# mLRS-dualE28-board02-v011.net
KiCad netlist of a schematic drawn in EAGLE
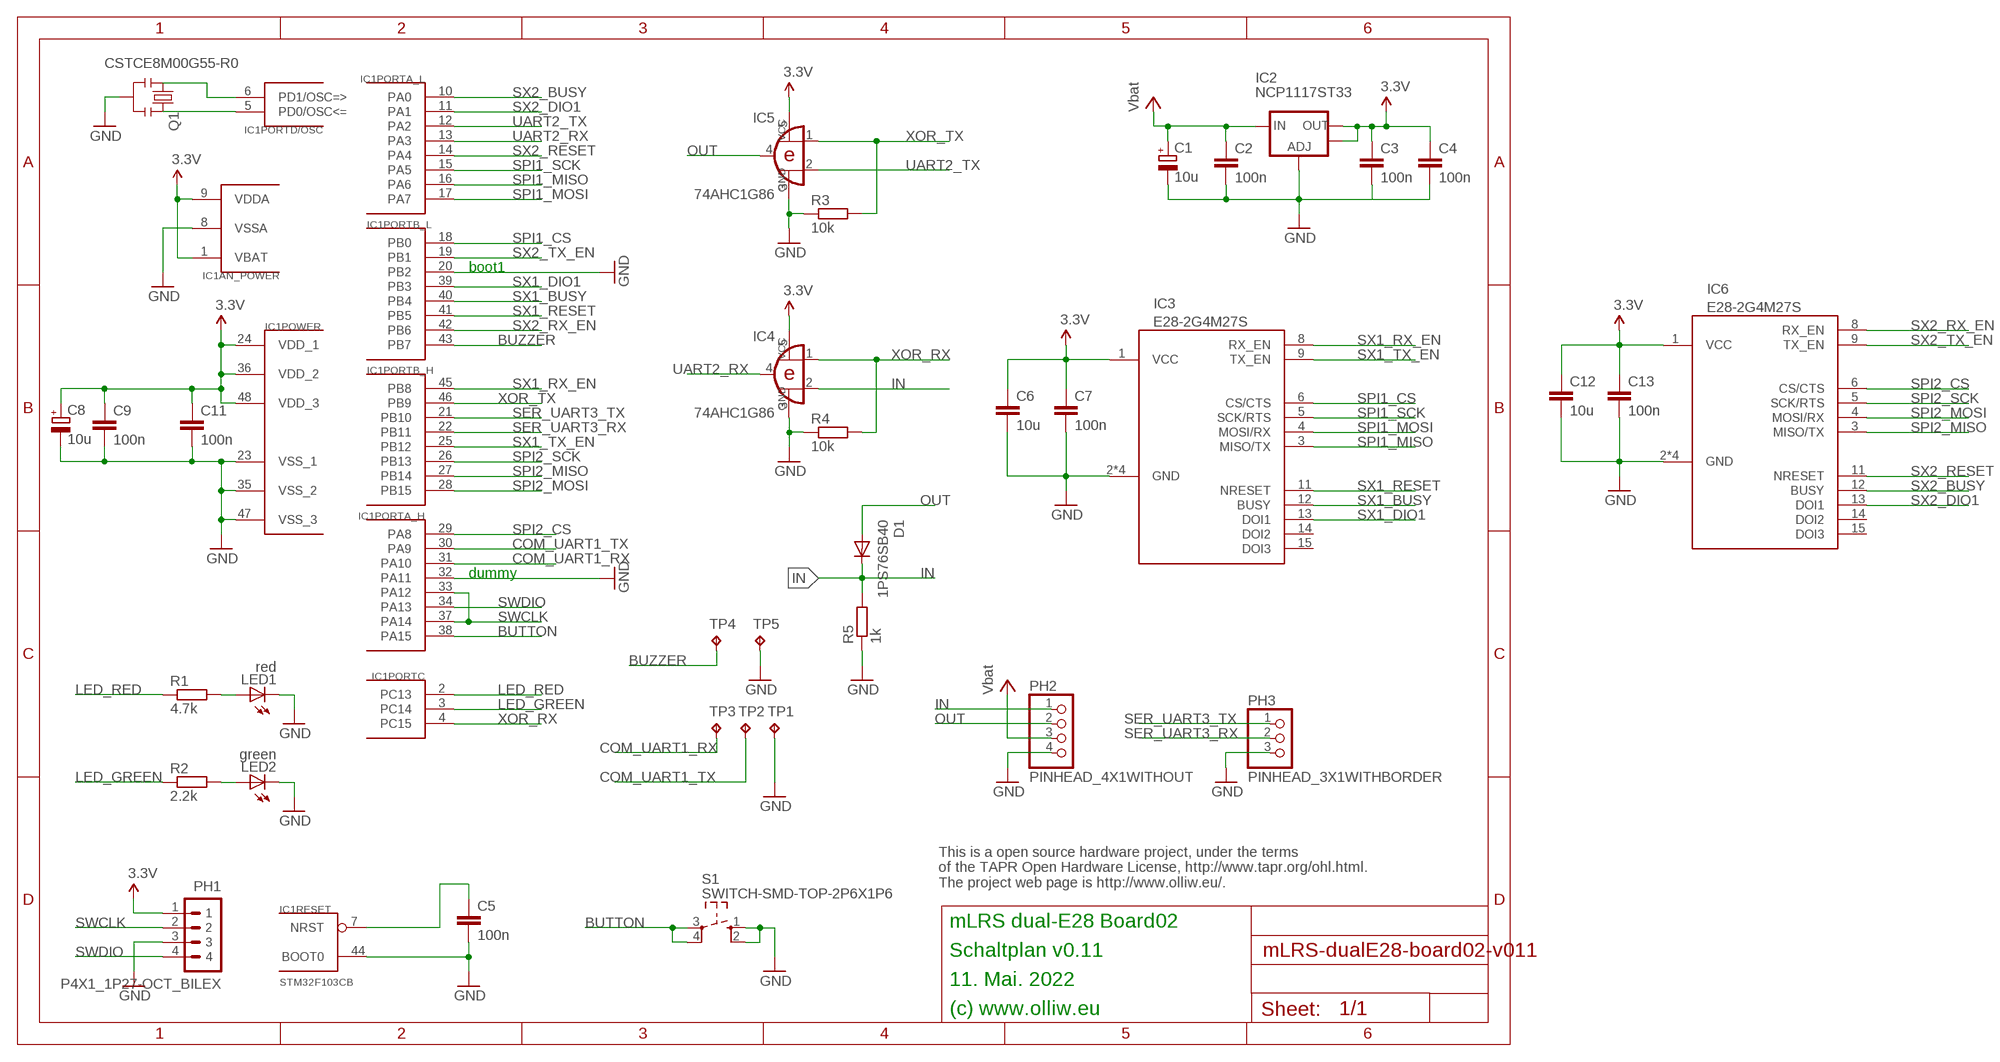
[diagram p0: schematic, sheet 1]

(export (version "E")
  (design (tool "Eeschema 10.0.6"))
  (components
    (comp (ref "C1")
      (value "10u")
      (footprint "eagle-import:SMC_A")
      (libsource (lib "eagle-import") (part "CPOL-EUSMCA"))
    )
    (comp (ref "C2")
      (value "100n")
      (footprint "eagle-import:C0603")
      (libsource (lib "eagle-import") (part "C-EUC0603"))
    )
    (comp (ref "C3")
      (value "100n")
      (footprint "eagle-import:C0402")
      (libsource (lib "eagle-import") (part "C-EUC0402"))
    )
    (comp (ref "C4")
      (value "100n")
      (footprint "eagle-import:C0402")
      (libsource (lib "eagle-import") (part "C-EUC0402"))
    )
    (comp (ref "C5")
      (value "100n")
      (footprint "eagle-import:C0402")
      (libsource (lib "eagle-import") (part "C-EUC0402"))
    )
    (comp (ref "C6")
      (value "10u")
      (footprint "eagle-import:C0603")
      (libsource (lib "eagle-import") (part "C-EUC0603"))
    )
    (comp (ref "C7")
      (value "100n")
      (footprint "eagle-import:C0402")
      (libsource (lib "eagle-import") (part "C-EUC0402"))
    )
    (comp (ref "C8")
      (value "10u")
      (footprint "eagle-import:SMC_A")
      (libsource (lib "eagle-import") (part "CPOL-EUSMCA"))
    )
    (comp (ref "C9")
      (value "100n")
      (footprint "eagle-import:C0402")
      (libsource (lib "eagle-import") (part "C-EUC0402"))
    )
    (comp (ref "C11")
      (value "100n")
      (footprint "eagle-import:C0402")
      (libsource (lib "eagle-import") (part "C-EUC0402"))
    )
    (comp (ref "C12")
      (value "10u")
      (footprint "eagle-import:C0603")
      (libsource (lib "eagle-import") (part "C-EUC0603"))
    )
    (comp (ref "C13")
      (value "100n")
      (footprint "eagle-import:C0402")
      (libsource (lib "eagle-import") (part "C-EUC0402"))
    )
    (comp (ref "D1")
      (value "1PS76SB40")
      (footprint "eagle-import:SOD110-R")
      (libsource (lib "eagle-import") (part "DIODE-SOD110-R"))
    )
    (comp (ref "IC1")
      (value "STM32F103CB")
      (footprint "eagle-import:TQFP48")
      (libsource (lib "eagle-import") (part "STM32F10XCXT6"))
    )
    (comp (ref "IC2")
      (value "NCP1117ST33")
      (footprint "eagle-import:SOT223")
      (libsource (lib "eagle-import") (part "V_REG_LM1117SOT223"))
    )
    (comp (ref "IC3")
      (value "E28-2G4M27S")
      (footprint "eagle-import:E28-2G4M27")
      (libsource (lib "eagle-import") (part "E28"))
    )
    (comp (ref "IC4")
      (value "74AHC1G86")
      (footprint "eagle-import:SOT23-5-VER1")
      (libsource (lib "eagle-import") (part "74AHC1G86"))
    )
    (comp (ref "IC5")
      (value "74AHC1G86")
      (footprint "eagle-import:SOT23-5-VER1")
      (libsource (lib "eagle-import") (part "74AHC1G86"))
    )
    (comp (ref "IC6")
      (value "E28-2G4M27S")
      (footprint "eagle-import:E28-2G4M27")
      (libsource (lib "eagle-import") (part "E28"))
    )
    (comp (ref "LED1")
      (value "red")
      (footprint "eagle-import:CHIPLED_0603")
      (libsource (lib "eagle-import") (part "LEDCHIPLED_0603"))
    )
    (comp (ref "LED2")
      (value "green")
      (footprint "eagle-import:CHIPLED_0603")
      (libsource (lib "eagle-import") (part "LEDCHIPLED_0603"))
    )
    (comp (ref "PH1")
      (value "P4X1_1P27-OCT_BILEX")
      (footprint "eagle-import:4X1_1P27_OCT_BILEX")
      (libsource (lib "eagle-import") (part "P4X1_1P27-OCT_BILEX"))
    )
    (comp (ref "PH2")
      (value "PINHEAD_4X1WITHOUT")
      (footprint "eagle-import:PINHEAD_4X1_WO")
      (libsource (lib "eagle-import") (part "PINHEAD_4X1WITHOUT"))
    )
    (comp (ref "PH3")
      (value "PINHEAD_3X1WITHBORDER")
      (footprint "eagle-import:PINHEAD_3X1")
      (libsource (lib "eagle-import") (part "PINHEAD_3X1WITHBORDER"))
    )
    (comp (ref "Q1")
      (value "CSTCE8M00G55-R0")
      (footprint "eagle-import:RESONATOR-SMD")
      (libsource (lib "eagle-import") (part "RESONATORSMD"))
    )
    (comp (ref "R1")
      (value "4.7k")
      (footprint "eagle-import:R0402")
      (libsource (lib "eagle-import") (part "R-EU_R0402"))
    )
    (comp (ref "R2")
      (value "2.2k")
      (footprint "eagle-import:R0402")
      (libsource (lib "eagle-import") (part "R-EU_R0402"))
    )
    (comp (ref "R3")
      (value "10k")
      (footprint "eagle-import:R0402")
      (libsource (lib "eagle-import") (part "R-EU_R0402"))
    )
    (comp (ref "R4")
      (value "10k")
      (footprint "eagle-import:R0402")
      (libsource (lib "eagle-import") (part "R-EU_R0402"))
    )
    (comp (ref "R5")
      (value "1k")
      (footprint "eagle-import:R0402")
      (libsource (lib "eagle-import") (part "R-EU_R0402"))
    )
    (comp (ref "S1")
      (value "SWITCH-SMD-TOP-2P6X1P6")
      (footprint "eagle-import:TACTILE-SWITCH-SMD-TOP-2P6X1X6")
      (libsource (lib "eagle-import") (part "SWITCH-SMD-TOP-2P6X1P6"))
    )
    (comp (ref "TP1")
      (value "TPB1,27")
      (footprint "eagle-import:B1,27")
      (libsource (lib "eagle-import") (part "TPB1,27"))
    )
    (comp (ref "TP2")
      (value "TPB1,27")
      (footprint "eagle-import:B1,27")
      (libsource (lib "eagle-import") (part "TPB1,27"))
    )
    (comp (ref "TP3")
      (value "TPB1,27")
      (footprint "eagle-import:B1,27")
      (libsource (lib "eagle-import") (part "TPB1,27"))
    )
    (comp (ref "TP4")
      (value "TPTP15R")
      (footprint "eagle-import:TP15R")
      (libsource (lib "eagle-import") (part "TPTP15R"))
    )
    (comp (ref "TP5")
      (value "TPTP15R")
      (footprint "eagle-import:TP15R")
      (libsource (lib "eagle-import") (part "TPTP15R"))
    )
  )
  (nets
    (net (code "1") (name "/BUTTON") (class "Default")
      (node (ref "IC1") (pin "38") (pinfunction "PA15_38") (pintype "bidirectional"))
      (node (ref "S1") (pin "3") (pinfunction "3_3") (pintype "passive"))
      (node (ref "S1") (pin "4") (pinfunction "4_4") (pintype "passive"))
    )
    (net (code "2") (name "/BUZZER") (class "Default")
      (node (ref "IC1") (pin "43") (pinfunction "PB7_43") (pintype "bidirectional"))
      (node (ref "TP4") (pin "TP") (pinfunction "TP_TP") (pintype "input"))
    )
    (net (code "3") (name "/COM_UART1_RX") (class "Default")
      (node (ref "IC1") (pin "31") (pinfunction "PA10_31") (pintype "bidirectional"))
      (node (ref "TP3") (pin "TP") (pinfunction "TP_TP") (pintype "input"))
    )
    (net (code "4") (name "/COM_UART1_TX") (class "Default")
      (node (ref "IC1") (pin "30") (pinfunction "PA9_30") (pintype "bidirectional"))
      (node (ref "TP2") (pin "TP") (pinfunction "TP_TP") (pintype "input"))
    )
    (net (code "5") (name "/LED_GREEN") (class "Default")
      (node (ref "IC1") (pin "3") (pinfunction "PC14_3") (pintype "bidirectional"))
      (node (ref "R2") (pin "1") (pinfunction "1_1") (pintype "passive"))
    )
    (net (code "6") (name "/LED_RED") (class "Default")
      (node (ref "IC1") (pin "2") (pinfunction "PC13_2") (pintype "bidirectional"))
      (node (ref "R1") (pin "1") (pinfunction "1_1") (pintype "passive"))
    )
    (net (code "7") (name "/OUT") (class "Default")
      (node (ref "D1") (pin "A") (pinfunction "A_A") (pintype "passive"))
      (node (ref "IC5") (pin "4") (pinfunction "O_4") (pintype "output"))
      (node (ref "PH2") (pin "2") (pinfunction "2_2") (pintype "passive"))
    )
    (net (code "8") (name "/SER_UART3_RX") (class "Default")
      (node (ref "IC1") (pin "22") (pinfunction "PB11_22") (pintype "bidirectional"))
      (node (ref "PH3") (pin "2") (pinfunction "3_2") (pintype "passive"))
    )
    (net (code "9") (name "/SER_UART3_TX") (class "Default")
      (node (ref "IC1") (pin "21") (pinfunction "PB10_21") (pintype "bidirectional"))
      (node (ref "PH3") (pin "1") (pinfunction "1_1") (pintype "passive"))
    )
    (net (code "10") (name "/SPI1_CS") (class "Default")
      (node (ref "IC1") (pin "18") (pinfunction "PB0_18") (pintype "bidirectional"))
      (node (ref "IC3") (pin "6") (pinfunction "CS/CTS_6") (pintype "bidirectional"))
    )
    (net (code "11") (name "/SPI1_MISO") (class "Default")
      (node (ref "IC1") (pin "16") (pinfunction "PA6_16") (pintype "bidirectional"))
      (node (ref "IC3") (pin "3") (pinfunction "MISO/TX_3") (pintype "bidirectional"))
    )
    (net (code "12") (name "/SPI1_MOSI") (class "Default")
      (node (ref "IC1") (pin "17") (pinfunction "PA7_17") (pintype "bidirectional"))
      (node (ref "IC3") (pin "4") (pinfunction "MOSI/RX_4") (pintype "bidirectional"))
    )
    (net (code "13") (name "/SPI1_SCK") (class "Default")
      (node (ref "IC1") (pin "15") (pinfunction "PA5_15") (pintype "bidirectional"))
      (node (ref "IC3") (pin "5") (pinfunction "SCK/RTS_5") (pintype "bidirectional"))
    )
    (net (code "14") (name "/SPI2_CS") (class "Default")
      (node (ref "IC1") (pin "29") (pinfunction "PA8_29") (pintype "bidirectional"))
      (node (ref "IC6") (pin "6") (pinfunction "CS/CTS_6") (pintype "bidirectional"))
    )
    (net (code "15") (name "/SPI2_MISO") (class "Default")
      (node (ref "IC1") (pin "27") (pinfunction "PB14_27") (pintype "bidirectional"))
      (node (ref "IC6") (pin "3") (pinfunction "MISO/TX_3") (pintype "bidirectional"))
    )
    (net (code "16") (name "/SPI2_MOSI") (class "Default")
      (node (ref "IC1") (pin "28") (pinfunction "PB15_28") (pintype "bidirectional"))
      (node (ref "IC6") (pin "4") (pinfunction "MOSI/RX_4") (pintype "bidirectional"))
    )
    (net (code "17") (name "/SPI2_SCK") (class "Default")
      (node (ref "IC1") (pin "26") (pinfunction "PB13_26") (pintype "bidirectional"))
      (node (ref "IC6") (pin "5") (pinfunction "SCK/RTS_5") (pintype "bidirectional"))
    )
    (net (code "18") (name "/SWCLK") (class "Default")
      (node (ref "IC1") (pin "33") (pinfunction "PA12_33") (pintype "bidirectional"))
      (node (ref "IC1") (pin "37") (pinfunction "PA14_37") (pintype "bidirectional"))
      (node (ref "PH1") (pin "2") (pinfunction "2_2") (pintype "passive"))
    )
    (net (code "19") (name "/SWDIO") (class "Default")
      (node (ref "IC1") (pin "34") (pinfunction "PA13_34") (pintype "bidirectional"))
      (node (ref "PH1") (pin "4") (pinfunction "4_4") (pintype "passive"))
    )
    (net (code "20") (name "/SX1_BUSY") (class "Default")
      (node (ref "IC1") (pin "40") (pinfunction "PB4_40") (pintype "bidirectional"))
      (node (ref "IC3") (pin "12") (pinfunction "BUSY_12") (pintype "bidirectional"))
    )
    (net (code "21") (name "/SX1_DIO1") (class "Default")
      (node (ref "IC1") (pin "39") (pinfunction "PB3_39") (pintype "bidirectional"))
      (node (ref "IC3") (pin "13") (pinfunction "DOI1_13") (pintype "bidirectional"))
    )
    (net (code "22") (name "/SX1_RESET") (class "Default")
      (node (ref "IC1") (pin "41") (pinfunction "PB5_41") (pintype "bidirectional"))
      (node (ref "IC3") (pin "11") (pinfunction "NRESET_11") (pintype "input"))
    )
    (net (code "23") (name "/SX1_RX_EN") (class "Default")
      (node (ref "IC1") (pin "45") (pinfunction "PB8_45") (pintype "bidirectional"))
      (node (ref "IC3") (pin "8") (pinfunction "RX_EN_8") (pintype "bidirectional"))
    )
    (net (code "24") (name "/SX1_TX_EN") (class "Default")
      (node (ref "IC1") (pin "25") (pinfunction "PB12_25") (pintype "bidirectional"))
      (node (ref "IC3") (pin "9") (pinfunction "TX_EN_9") (pintype "bidirectional"))
    )
    (net (code "25") (name "/SX2_BUSY") (class "Default")
      (node (ref "IC1") (pin "10") (pinfunction "PA0_10") (pintype "bidirectional"))
      (node (ref "IC6") (pin "12") (pinfunction "BUSY_12") (pintype "bidirectional"))
    )
    (net (code "26") (name "/SX2_DIO1") (class "Default")
      (node (ref "IC1") (pin "11") (pinfunction "PA1_11") (pintype "bidirectional"))
      (node (ref "IC6") (pin "13") (pinfunction "DOI1_13") (pintype "bidirectional"))
    )
    (net (code "27") (name "/SX2_RESET") (class "Default")
      (node (ref "IC1") (pin "14") (pinfunction "PA4_14") (pintype "bidirectional"))
      (node (ref "IC6") (pin "11") (pinfunction "NRESET_11") (pintype "input"))
    )
    (net (code "28") (name "/SX2_RX_EN") (class "Default")
      (node (ref "IC1") (pin "42") (pinfunction "PB6_42") (pintype "bidirectional"))
      (node (ref "IC6") (pin "8") (pinfunction "RX_EN_8") (pintype "bidirectional"))
    )
    (net (code "29") (name "/SX2_TX_EN") (class "Default")
      (node (ref "IC1") (pin "19") (pinfunction "PB1_19") (pintype "bidirectional"))
      (node (ref "IC6") (pin "9") (pinfunction "TX_EN_9") (pintype "bidirectional"))
    )
    (net (code "30") (name "/UART2_RX") (class "Default")
      (node (ref "IC1") (pin "13") (pinfunction "PA3_13") (pintype "bidirectional"))
      (node (ref "IC4") (pin "4") (pinfunction "O_4") (pintype "output"))
    )
    (net (code "31") (name "/UART2_TX") (class "Default")
      (node (ref "IC1") (pin "12") (pinfunction "PA2_12") (pintype "bidirectional"))
      (node (ref "IC5") (pin "2") (pinfunction "I1_2") (pintype "input"))
    )
    (net (code "32") (name "/XOR_RX") (class "Default")
      (node (ref "IC1") (pin "4") (pinfunction "PC15_4") (pintype "bidirectional"))
      (node (ref "IC4") (pin "1") (pinfunction "I0_1") (pintype "input"))
      (node (ref "R4") (pin "2") (pinfunction "2_2") (pintype "passive"))
    )
    (net (code "33") (name "/XOR_TX") (class "Default")
      (node (ref "IC1") (pin "46") (pinfunction "PB9_46") (pintype "bidirectional"))
      (node (ref "IC5") (pin "1") (pinfunction "I0_1") (pintype "input"))
      (node (ref "R3") (pin "2") (pinfunction "2_2") (pintype "passive"))
    )
    (net (code "34") (name "3.3V") (class "Default")
      (node (ref "C11") (pin "1") (pinfunction "1_1") (pintype "passive"))
      (node (ref "C12") (pin "1") (pinfunction "1_1") (pintype "passive"))
      (node (ref "C13") (pin "1") (pinfunction "1_1") (pintype "passive"))
      (node (ref "C3") (pin "1") (pinfunction "1_1") (pintype "passive"))
      (node (ref "C4") (pin "1") (pinfunction "1_1") (pintype "passive"))
      (node (ref "C6") (pin "1") (pinfunction "1_1") (pintype "passive"))
      (node (ref "C7") (pin "1") (pinfunction "1_1") (pintype "passive"))
      (node (ref "C8") (pin "+") (pinfunction "+_+") (pintype "passive"))
      (node (ref "C9") (pin "1") (pinfunction "1_1") (pintype "passive"))
      (node (ref "IC1") (pin "1") (pinfunction "VBAT_1") (pintype "power_in"))
      (node (ref "IC1") (pin "24") (pinfunction "VDD_1_24") (pintype "power_in"))
      (node (ref "IC1") (pin "36") (pinfunction "VDD_2_36") (pintype "power_in"))
      (node (ref "IC1") (pin "48") (pinfunction "VDD_3_48") (pintype "power_in"))
      (node (ref "IC1") (pin "9") (pinfunction "VDDA_9") (pintype "power_in"))
      (node (ref "IC2") (pin "2") (pinfunction "OUT_2") (pintype "output"))
      (node (ref "IC2") (pin "4") (pinfunction "OUT_4") (pintype "output"))
      (node (ref "IC3") (pin "1") (pinfunction "VCC_1") (pintype "power_in"))
      (node (ref "IC4") (pin "5") (pinfunction "VCC_5") (pintype "power_in"))
      (node (ref "IC5") (pin "5") (pinfunction "VCC_5") (pintype "power_in"))
      (node (ref "IC6") (pin "1") (pinfunction "VCC_1") (pintype "power_in"))
      (node (ref "PH1") (pin "1") (pinfunction "1_1") (pintype "passive"))
    )
    (net (code "35") (name "GND") (class "Default")
      (node (ref "C1") (pin "-") (pinfunction "-_-") (pintype "passive"))
      (node (ref "C11") (pin "2") (pinfunction "2_2") (pintype "passive"))
      (node (ref "C12") (pin "2") (pinfunction "2_2") (pintype "passive"))
      (node (ref "C13") (pin "2") (pinfunction "2_2") (pintype "passive"))
      (node (ref "C2") (pin "2") (pinfunction "2_2") (pintype "passive"))
      (node (ref "C3") (pin "2") (pinfunction "2_2") (pintype "passive"))
      (node (ref "C4") (pin "2") (pinfunction "2_2") (pintype "passive"))
      (node (ref "C5") (pin "2") (pinfunction "2_2") (pintype "passive"))
      (node (ref "C6") (pin "2") (pinfunction "2_2") (pintype "passive"))
      (node (ref "C7") (pin "2") (pinfunction "2_2") (pintype "passive"))
      (node (ref "C8") (pin "-") (pinfunction "-_-") (pintype "passive"))
      (node (ref "C9") (pin "2") (pinfunction "2_2") (pintype "passive"))
      (node (ref "IC1") (pin "20") (pinfunction "PB2_20") (pintype "bidirectional"))
      (node (ref "IC1") (pin "23") (pinfunction "VSS_1_23") (pintype "power_in"))
      (node (ref "IC1") (pin "32") (pinfunction "PA11_32") (pintype "bidirectional"))
      (node (ref "IC1") (pin "35") (pinfunction "VSS_2_35") (pintype "power_in"))
      (node (ref "IC1") (pin "44") (pinfunction "BOOT0_44") (pintype "input"))
      (node (ref "IC1") (pin "47") (pinfunction "VSS_3_47") (pintype "power_in"))
      (node (ref "IC1") (pin "8") (pinfunction "VSSA_8") (pintype "power_in"))
      (node (ref "IC2") (pin "1") (pinfunction "ADJ_1") (pintype "input"))
      (node (ref "IC3") (pin "10") (pinfunction "GND_10") (pintype "power_in"))
      (node (ref "IC3") (pin "16") (pinfunction "GND_16") (pintype "power_in"))
      (node (ref "IC3") (pin "2") (pinfunction "GND_2") (pintype "power_in"))
      (node (ref "IC3") (pin "7") (pinfunction "GND_7") (pintype "power_in"))
      (node (ref "IC4") (pin "3") (pinfunction "GND_3") (pintype "power_in"))
      (node (ref "IC5") (pin "3") (pinfunction "GND_3") (pintype "power_in"))
      (node (ref "IC6") (pin "10") (pinfunction "GND_10") (pintype "power_in"))
      (node (ref "IC6") (pin "16") (pinfunction "GND_16") (pintype "power_in"))
      (node (ref "IC6") (pin "2") (pinfunction "GND_2") (pintype "power_in"))
      (node (ref "IC6") (pin "7") (pinfunction "GND_7") (pintype "power_in"))
      (node (ref "LED1") (pin "C") (pinfunction "C_C") (pintype "passive"))
      (node (ref "LED2") (pin "C") (pinfunction "C_C") (pintype "passive"))
      (node (ref "PH1") (pin "3") (pinfunction "3_3") (pintype "passive"))
      (node (ref "PH2") (pin "4") (pinfunction "4_4") (pintype "passive"))
      (node (ref "PH3") (pin "3") (pinfunction "5_3") (pintype "passive"))
      (node (ref "Q1") (pin "2") (pinfunction "2_2") (pintype "passive"))
      (node (ref "R3") (pin "1") (pinfunction "1_1") (pintype "passive"))
      (node (ref "R4") (pin "1") (pinfunction "1_1") (pintype "passive"))
      (node (ref "R5") (pin "1") (pinfunction "1_1") (pintype "passive"))
      (node (ref "S1") (pin "1") (pinfunction "1_1") (pintype "passive"))
      (node (ref "S1") (pin "2") (pinfunction "2_2") (pintype "passive"))
      (node (ref "TP1") (pin "TP") (pinfunction "TP_TP") (pintype "input"))
      (node (ref "TP5") (pin "TP") (pinfunction "TP_TP") (pintype "input"))
    )
    (net (code "36") (name "IN") (class "Default")
      (node (ref "D1") (pin "C") (pinfunction "C_C") (pintype "passive"))
      (node (ref "IC4") (pin "2") (pinfunction "I1_2") (pintype "input"))
      (node (ref "PH2") (pin "1") (pinfunction "1_1") (pintype "passive"))
      (node (ref "R5") (pin "2") (pinfunction "2_2") (pintype "passive"))
    )
    (net (code "37") (name "Net-(IC1G-PD0{slash}OSC<=)") (class "Default")
      (node (ref "IC1") (pin "5") (pinfunction "PD0/OSC<=_5") (pintype "bidirectional"))
      (node (ref "Q1") (pin "3") (pinfunction "3_3") (pintype "passive"))
    )
    (net (code "38") (name "Net-(IC1G-PD1{slash}OSC=>)") (class "Default")
      (node (ref "IC1") (pin "6") (pinfunction "PD1/OSC=>_6") (pintype "bidirectional"))
      (node (ref "Q1") (pin "1") (pinfunction "1_1") (pintype "passive"))
    )
    (net (code "39") (name "Net-(IC1I-NRST)") (class "Default")
      (node (ref "C5") (pin "1") (pinfunction "1_1") (pintype "passive"))
      (node (ref "IC1") (pin "7") (pinfunction "NRST_7") (pintype "input"))
    )
    (net (code "40") (name "Net-(LED1-PadA)") (class "Default")
      (node (ref "LED1") (pin "A") (pinfunction "A_A") (pintype "passive"))
      (node (ref "R1") (pin "2") (pinfunction "2_2") (pintype "passive"))
    )
    (net (code "41") (name "Net-(LED2-PadA)") (class "Default")
      (node (ref "LED2") (pin "A") (pinfunction "A_A") (pintype "passive"))
      (node (ref "R2") (pin "2") (pinfunction "2_2") (pintype "passive"))
    )
    (net (code "42") (name "Vbat") (class "Default")
      (node (ref "C1") (pin "+") (pinfunction "+_+") (pintype "passive"))
      (node (ref "C2") (pin "1") (pinfunction "1_1") (pintype "passive"))
      (node (ref "IC2") (pin "3") (pinfunction "IN_3") (pintype "input"))
      (node (ref "PH2") (pin "3") (pinfunction "3_3") (pintype "passive"))
    )
    (net (code "43") (name "unconnected-(IC3-DOI2-Pad14)") (class "Default")
      (node (ref "IC3") (pin "14") (pinfunction "DOI2_14") (pintype "bidirectional"))
    )
    (net (code "44") (name "unconnected-(IC3-DOI3-Pad15)") (class "Default")
      (node (ref "IC3") (pin "15") (pinfunction "DOI3_15") (pintype "bidirectional"))
    )
    (net (code "45") (name "unconnected-(IC6-DOI2-Pad14)") (class "Default")
      (node (ref "IC6") (pin "14") (pinfunction "DOI2_14") (pintype "bidirectional"))
    )
    (net (code "46") (name "unconnected-(IC6-DOI3-Pad15)") (class "Default")
      (node (ref "IC6") (pin "15") (pinfunction "DOI3_15") (pintype "bidirectional"))
    )
  )
)
